# BNO055I_MS5637MiniTeensyShieldv01y.net
KiCad netlist of a schematic drawn in EAGLE
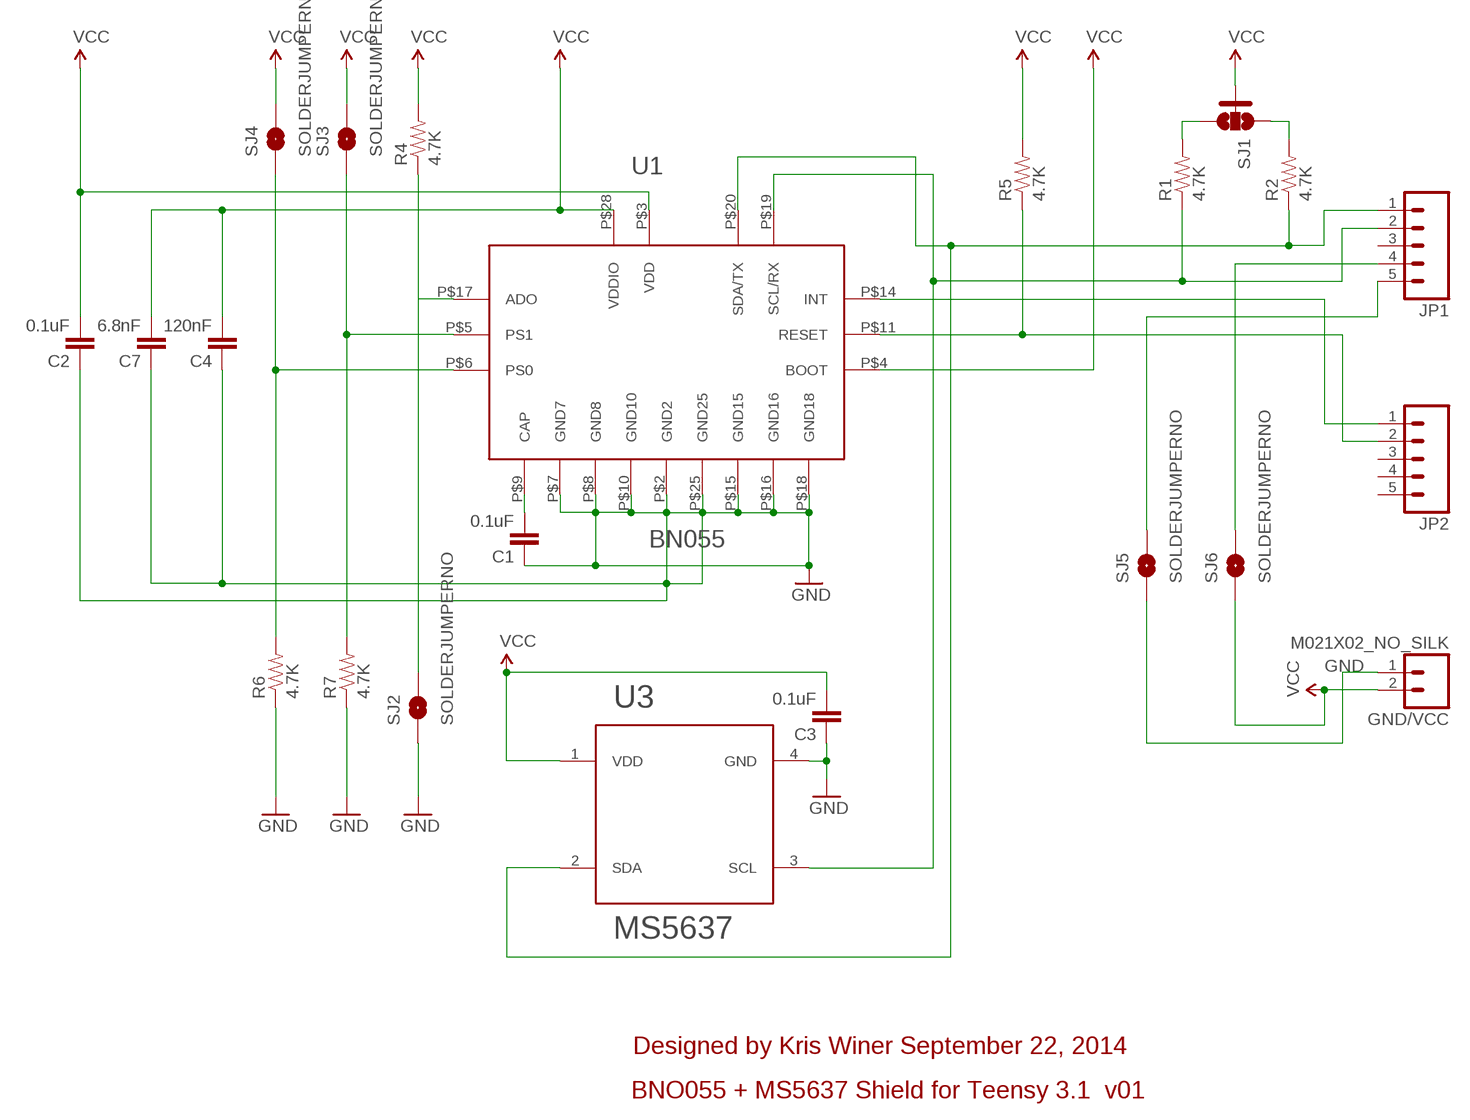
[diagram p0: schematic, sheet 1]

(export (version "E")
  (design (tool "Eeschema 10.0.6"))
  (components
    (comp (ref "C1")
      (value "0.1uF")
      (footprint "eagle-import:0603-CAP")
      (libsource (lib "eagle-import") (part "0.22UF-25V-10%(0603)"))
    )
    (comp (ref "C2")
      (value "0.1uF")
      (footprint "eagle-import:0603-CAP")
      (libsource (lib "eagle-import") (part "0.22UF-25V-10%(0603)"))
    )
    (comp (ref "C3")
      (value "0.1uF")
      (footprint "eagle-import:0603-CAP")
      (libsource (lib "eagle-import") (part "0.22UF-25V-10%(0603)"))
    )
    (comp (ref "C4")
      (value "120nF")
      (footprint "eagle-import:0603-CAP")
      (libsource (lib "eagle-import") (part "0.22UF-25V-10%(0603)"))
    )
    (comp (ref "C7")
      (value "6.8nF")
      (footprint "eagle-import:0603-CAP")
      (libsource (lib "eagle-import") (part "0.22UF-25V-10%(0603)"))
    )
    (comp (ref "GND/VCC")
      (value "M021X02_NO_SILK")
      (footprint "eagle-import:1X02_NO_SILK")
      (libsource (lib "eagle-import") (part "M021X02_NO_SILK"))
    )
    (comp (ref "JP1")
      (value "M05NO_SILK")
      (footprint "eagle-import:1X05_NO_SILK")
      (libsource (lib "eagle-import") (part "M05NO_SILK"))
    )
    (comp (ref "JP2")
      (value "M05NO_SILK")
      (footprint "eagle-import:1X05_NO_SILK")
      (libsource (lib "eagle-import") (part "M05NO_SILK"))
    )
    (comp (ref "R1")
      (value "4.7K")
      (footprint "eagle-import:0603-RES")
      (libsource (lib "eagle-import") (part "10K-1%RES-00824"))
    )
    (comp (ref "R2")
      (value "4.7K")
      (footprint "eagle-import:0603-RES")
      (libsource (lib "eagle-import") (part "10K-1%RES-00824"))
    )
    (comp (ref "R4")
      (value "4.7K")
      (footprint "eagle-import:0603-RES")
      (libsource (lib "eagle-import") (part "10K-1%RES-00824"))
    )
    (comp (ref "R5")
      (value "4.7K")
      (footprint "eagle-import:0603-RES")
      (libsource (lib "eagle-import") (part "10K-1%RES-00824"))
    )
    (comp (ref "R6")
      (value "4.7K")
      (footprint "eagle-import:0603-RES")
      (libsource (lib "eagle-import") (part "10K-1%RES-00824"))
    )
    (comp (ref "R7")
      (value "4.7K")
      (footprint "eagle-import:0603-RES")
      (libsource (lib "eagle-import") (part "10K-1%RES-00824"))
    )
    (comp (ref "SJ1")
      (value "SOLDERJUMPER_2WAYS")
      (footprint "eagle-import:SJ_3")
      (libsource (lib "eagle-import") (part "SOLDERJUMPER_2WAYS"))
    )
    (comp (ref "SJ2")
      (value "SOLDERJUMPERNO")
      (footprint "eagle-import:SJ_2S-NO")
      (libsource (lib "eagle-import") (part "SOLDERJUMPERNO"))
    )
    (comp (ref "SJ3")
      (value "SOLDERJUMPERNO")
      (footprint "eagle-import:SJ_2S-NO")
      (libsource (lib "eagle-import") (part "SOLDERJUMPERNO"))
    )
    (comp (ref "SJ4")
      (value "SOLDERJUMPERNO")
      (footprint "eagle-import:SJ_2S-NO")
      (libsource (lib "eagle-import") (part "SOLDERJUMPERNO"))
    )
    (comp (ref "SJ5")
      (value "SOLDERJUMPERNO")
      (footprint "eagle-import:SJ_2S-NO")
      (libsource (lib "eagle-import") (part "SOLDERJUMPERNO"))
    )
    (comp (ref "SJ6")
      (value "SOLDERJUMPERNO")
      (footprint "eagle-import:SJ_2S-NO")
      (libsource (lib "eagle-import") (part "SOLDERJUMPERNO"))
    )
    (comp (ref "U1")
      (value "BN055")
      (footprint "eagle-import:LGA28")
      (libsource (lib "eagle-import") (part "BN055"))
    )
    (comp (ref "U3")
      (value "MS5637")
      (footprint "eagle-import:MS5637QFN-4")
      (libsource (lib "eagle-import") (part "MS5637"))
    )
  )
  (nets
    (net (code "1") (name "GND") (class "Default")
      (node (ref "C1") (pin "1") (pinfunction "1_1") (pintype "passive"))
      (node (ref "C2") (pin "1") (pinfunction "1_1") (pintype "passive"))
      (node (ref "C3") (pin "1") (pinfunction "1_1") (pintype "passive"))
      (node (ref "C4") (pin "1") (pinfunction "1_1") (pintype "passive"))
      (node (ref "C7") (pin "1") (pinfunction "1_1") (pintype "passive"))
      (node (ref "GND/VCC") (pin "1") (pinfunction "1_1") (pintype "passive"))
      (node (ref "R6") (pin "1") (pinfunction "1_1") (pintype "passive"))
      (node (ref "R7") (pin "1") (pinfunction "1_1") (pintype "passive"))
      (node (ref "SJ2") (pin "1") (pinfunction "1_1") (pintype "passive"))
      (node (ref "SJ5") (pin "1") (pinfunction "1_1") (pintype "passive"))
      (node (ref "U1") (pin "P$10") (pinfunction "GND10_P$10") (pintype "power_in"))
      (node (ref "U1") (pin "P$15") (pinfunction "GND15_P$15") (pintype "power_in"))
      (node (ref "U1") (pin "P$16") (pinfunction "GND16_P$16") (pintype "power_in"))
      (node (ref "U1") (pin "P$18") (pinfunction "GND18_P$18") (pintype "power_in"))
      (node (ref "U1") (pin "P$2") (pinfunction "GND2_P$2") (pintype "power_in"))
      (node (ref "U1") (pin "P$25") (pinfunction "GND25_P$25") (pintype "power_in"))
      (node (ref "U1") (pin "P$7") (pinfunction "GND7_P$7") (pintype "power_in"))
      (node (ref "U1") (pin "P$8") (pinfunction "GND8_P$8") (pintype "power_in"))
      (node (ref "U3") (pin "4") (pinfunction "GND_4") (pintype "power_in"))
    )
    (net (code "2") (name "Net-(JP1-Pad4)") (class "Default")
      (node (ref "JP1") (pin "4") (pinfunction "4_4") (pintype "passive"))
      (node (ref "SJ6") (pin "2") (pinfunction "2_2") (pintype "passive"))
    )
    (net (code "3") (name "Net-(JP1-Pad5)") (class "Default")
      (node (ref "JP1") (pin "5") (pinfunction "5_5") (pintype "passive"))
      (node (ref "SJ5") (pin "2") (pinfunction "2_2") (pintype "passive"))
    )
    (net (code "4") (name "Net-(R1-Pad2)") (class "Default")
      (node (ref "R1") (pin "2") (pinfunction "2_2") (pintype "passive"))
      (node (ref "SJ1") (pin "3") (pinfunction "3_3") (pintype "passive"))
    )
    (net (code "5") (name "Net-(R2-Pad2)") (class "Default")
      (node (ref "R2") (pin "2") (pinfunction "2_2") (pintype "passive"))
      (node (ref "SJ1") (pin "1") (pinfunction "1_1") (pintype "passive"))
    )
    (net (code "6") (name "Net-(U1-ADO)") (class "Default")
      (node (ref "R4") (pin "1") (pinfunction "1_1") (pintype "passive"))
      (node (ref "SJ2") (pin "2") (pinfunction "2_2") (pintype "passive"))
      (node (ref "U1") (pin "P$17") (pinfunction "ADO_P$17") (pintype "bidirectional"))
    )
    (net (code "7") (name "Net-(U1-CAP)") (class "Default")
      (node (ref "C1") (pin "2") (pinfunction "2_2") (pintype "passive"))
      (node (ref "U1") (pin "P$9") (pinfunction "CAP_P$9") (pintype "power_in"))
    )
    (net (code "8") (name "Net-(U1-INT)") (class "Default")
      (node (ref "JP2") (pin "1") (pinfunction "1_1") (pintype "passive"))
      (node (ref "U1") (pin "P$14") (pinfunction "INT_P$14") (pintype "bidirectional"))
    )
    (net (code "9") (name "Net-(U1-PS0)") (class "Default")
      (node (ref "R6") (pin "2") (pinfunction "2_2") (pintype "passive"))
      (node (ref "SJ4") (pin "1") (pinfunction "1_1") (pintype "passive"))
      (node (ref "U1") (pin "P$6") (pinfunction "PS0_P$6") (pintype "bidirectional"))
    )
    (net (code "10") (name "Net-(U1-PS1)") (class "Default")
      (node (ref "R7") (pin "2") (pinfunction "2_2") (pintype "passive"))
      (node (ref "SJ3") (pin "1") (pinfunction "1_1") (pintype "passive"))
      (node (ref "U1") (pin "P$5") (pinfunction "PS1_P$5") (pintype "bidirectional"))
    )
    (net (code "11") (name "Net-(U1-RESET)") (class "Default")
      (node (ref "JP2") (pin "2") (pinfunction "2_2") (pintype "passive"))
      (node (ref "R5") (pin "1") (pinfunction "1_1") (pintype "passive"))
      (node (ref "U1") (pin "P$11") (pinfunction "RESET_P$11") (pintype "bidirectional"))
    )
    (net (code "12") (name "Net-(U1-SCL{slash}RX)") (class "Default")
      (node (ref "JP1") (pin "2") (pinfunction "2_2") (pintype "passive"))
      (node (ref "R1") (pin "1") (pinfunction "1_1") (pintype "passive"))
      (node (ref "U1") (pin "P$19") (pinfunction "SCL/RX_P$19") (pintype "bidirectional"))
      (node (ref "U3") (pin "3") (pinfunction "SCL_3") (pintype "bidirectional"))
    )
    (net (code "13") (name "Net-(U1-SDA{slash}TX)") (class "Default")
      (node (ref "JP1") (pin "1") (pinfunction "1_1") (pintype "passive"))
      (node (ref "R2") (pin "1") (pinfunction "1_1") (pintype "passive"))
      (node (ref "U1") (pin "P$20") (pinfunction "SDA/TX_P$20") (pintype "bidirectional"))
      (node (ref "U3") (pin "2") (pinfunction "SDA_2") (pintype "bidirectional"))
    )
    (net (code "14") (name "VCC") (class "Default")
      (node (ref "C2") (pin "2") (pinfunction "2_2") (pintype "passive"))
      (node (ref "C3") (pin "2") (pinfunction "2_2") (pintype "passive"))
      (node (ref "C4") (pin "2") (pinfunction "2_2") (pintype "passive"))
      (node (ref "C7") (pin "2") (pinfunction "2_2") (pintype "passive"))
      (node (ref "GND/VCC") (pin "2") (pinfunction "2_2") (pintype "passive"))
      (node (ref "R4") (pin "2") (pinfunction "2_2") (pintype "passive"))
      (node (ref "R5") (pin "2") (pinfunction "2_2") (pintype "passive"))
      (node (ref "SJ1") (pin "2") (pinfunction "2_2") (pintype "passive"))
      (node (ref "SJ3") (pin "2") (pinfunction "2_2") (pintype "passive"))
      (node (ref "SJ4") (pin "2") (pinfunction "2_2") (pintype "passive"))
      (node (ref "SJ6") (pin "1") (pinfunction "1_1") (pintype "passive"))
      (node (ref "U1") (pin "P$28") (pinfunction "VDDIO_P$28") (pintype "power_in"))
      (node (ref "U1") (pin "P$3") (pinfunction "VDD_P$3") (pintype "power_in"))
      (node (ref "U1") (pin "P$4") (pinfunction "BOOT_P$4") (pintype "bidirectional"))
      (node (ref "U3") (pin "1") (pinfunction "VDD_1") (pintype "power_in"))
    )
    (net (code "15") (name "unconnected-(JP1-Pad3)") (class "Default")
      (node (ref "JP1") (pin "3") (pinfunction "3_3") (pintype "passive"))
    )
    (net (code "16") (name "unconnected-(JP2-Pad3)") (class "Default")
      (node (ref "JP2") (pin "3") (pinfunction "3_3") (pintype "passive"))
    )
    (net (code "17") (name "unconnected-(JP2-Pad4)") (class "Default")
      (node (ref "JP2") (pin "4") (pinfunction "4_4") (pintype "passive"))
    )
    (net (code "18") (name "unconnected-(JP2-Pad5)") (class "Default")
      (node (ref "JP2") (pin "5") (pinfunction "5_5") (pintype "passive"))
    )
  )
)
